# lautnerv.net
KiCad netlist of a schematic drawn in EAGLE
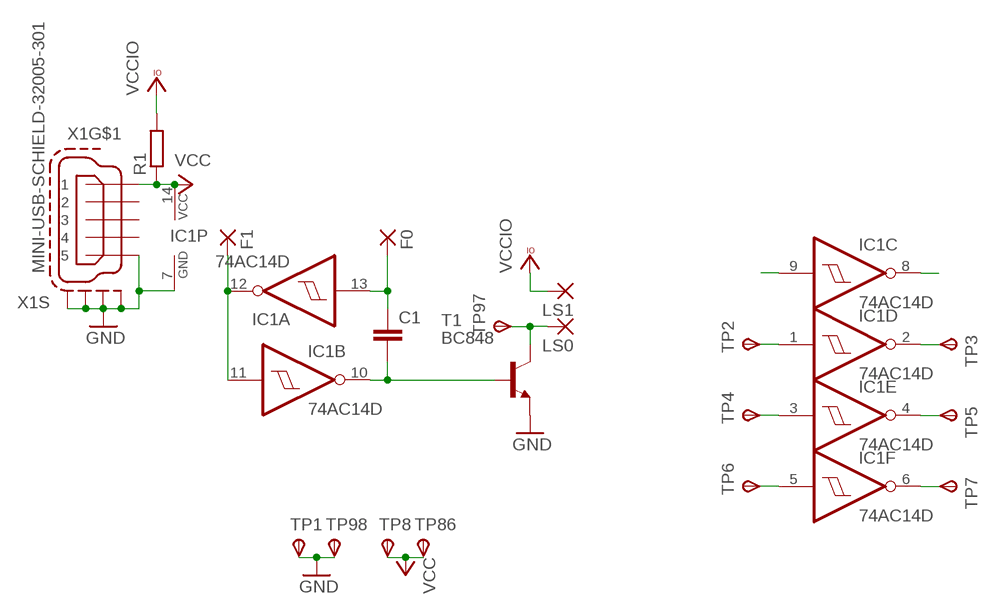
[diagram p0: schematic, sheet 1]
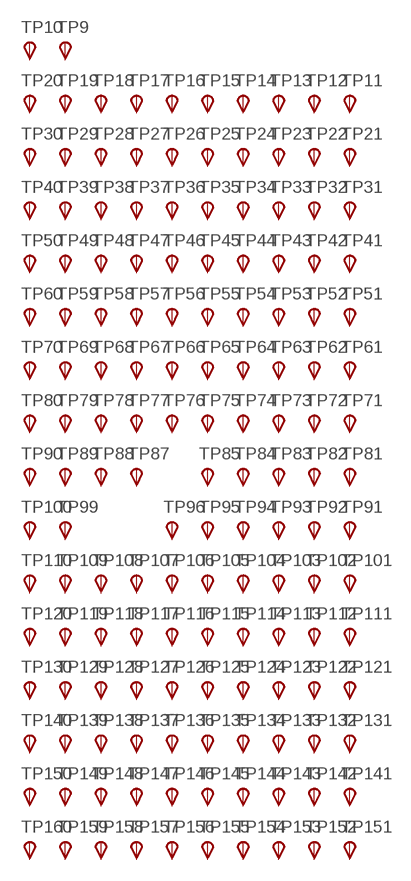
[diagram p1: schematic, sheet 2]

(export (version "E")
  (design (tool "Eeschema 10.0.6"))
  (components
    (comp (ref "TP9")
      (value "TPSTP12SQ")
      (footprint "eagle-import:TP12SQ")
      (libsource (lib "eagle-import") (part "TPSTP12SQ"))
    )
    (comp (ref "TP10")
      (value "TPSTP12SQ")
      (footprint "eagle-import:TP12SQ")
      (libsource (lib "eagle-import") (part "TPSTP12SQ"))
    )
    (comp (ref "TP11")
      (value "TPSTP12SQ")
      (footprint "eagle-import:TP12SQ")
      (libsource (lib "eagle-import") (part "TPSTP12SQ"))
    )
    (comp (ref "TP12")
      (value "TPSTP12SQ")
      (footprint "eagle-import:TP12SQ")
      (libsource (lib "eagle-import") (part "TPSTP12SQ"))
    )
    (comp (ref "TP13")
      (value "TPSTP12SQ")
      (footprint "eagle-import:TP12SQ")
      (libsource (lib "eagle-import") (part "TPSTP12SQ"))
    )
    (comp (ref "TP14")
      (value "TPSTP12SQ")
      (footprint "eagle-import:TP12SQ")
      (libsource (lib "eagle-import") (part "TPSTP12SQ"))
    )
    (comp (ref "TP15")
      (value "TPSTP12SQ")
      (footprint "eagle-import:TP12SQ")
      (libsource (lib "eagle-import") (part "TPSTP12SQ"))
    )
    (comp (ref "TP16")
      (value "TPSTP12SQ")
      (footprint "eagle-import:TP12SQ")
      (libsource (lib "eagle-import") (part "TPSTP12SQ"))
    )
    (comp (ref "TP17")
      (value "TPSTP12SQ")
      (footprint "eagle-import:TP12SQ")
      (libsource (lib "eagle-import") (part "TPSTP12SQ"))
    )
    (comp (ref "TP18")
      (value "TPSTP12SQ")
      (footprint "eagle-import:TP12SQ")
      (libsource (lib "eagle-import") (part "TPSTP12SQ"))
    )
    (comp (ref "TP19")
      (value "TPSTP12SQ")
      (footprint "eagle-import:TP12SQ")
      (libsource (lib "eagle-import") (part "TPSTP12SQ"))
    )
    (comp (ref "TP20")
      (value "TPSTP12SQ")
      (footprint "eagle-import:TP12SQ")
      (libsource (lib "eagle-import") (part "TPSTP12SQ"))
    )
    (comp (ref "TP21")
      (value "TPSTP12SQ")
      (footprint "eagle-import:TP12SQ")
      (libsource (lib "eagle-import") (part "TPSTP12SQ"))
    )
    (comp (ref "TP22")
      (value "TPSTP12SQ")
      (footprint "eagle-import:TP12SQ")
      (libsource (lib "eagle-import") (part "TPSTP12SQ"))
    )
    (comp (ref "TP23")
      (value "TPSTP12SQ")
      (footprint "eagle-import:TP12SQ")
      (libsource (lib "eagle-import") (part "TPSTP12SQ"))
    )
    (comp (ref "TP24")
      (value "TPSTP12SQ")
      (footprint "eagle-import:TP12SQ")
      (libsource (lib "eagle-import") (part "TPSTP12SQ"))
    )
    (comp (ref "TP25")
      (value "TPSTP12SQ")
      (footprint "eagle-import:TP12SQ")
      (libsource (lib "eagle-import") (part "TPSTP12SQ"))
    )
    (comp (ref "TP26")
      (value "TPSTP12SQ")
      (footprint "eagle-import:TP12SQ")
      (libsource (lib "eagle-import") (part "TPSTP12SQ"))
    )
    (comp (ref "TP27")
      (value "TPSTP12SQ")
      (footprint "eagle-import:TP12SQ")
      (libsource (lib "eagle-import") (part "TPSTP12SQ"))
    )
    (comp (ref "TP28")
      (value "TPSTP12SQ")
      (footprint "eagle-import:TP12SQ")
      (libsource (lib "eagle-import") (part "TPSTP12SQ"))
    )
    (comp (ref "TP29")
      (value "TPSTP12SQ")
      (footprint "eagle-import:TP12SQ")
      (libsource (lib "eagle-import") (part "TPSTP12SQ"))
    )
    (comp (ref "TP30")
      (value "TPSTP12SQ")
      (footprint "eagle-import:TP12SQ")
      (libsource (lib "eagle-import") (part "TPSTP12SQ"))
    )
    (comp (ref "TP31")
      (value "TPSTP12SQ")
      (footprint "eagle-import:TP12SQ")
      (libsource (lib "eagle-import") (part "TPSTP12SQ"))
    )
    (comp (ref "TP32")
      (value "TPSTP12SQ")
      (footprint "eagle-import:TP12SQ")
      (libsource (lib "eagle-import") (part "TPSTP12SQ"))
    )
    (comp (ref "TP33")
      (value "TPSTP12SQ")
      (footprint "eagle-import:TP12SQ")
      (libsource (lib "eagle-import") (part "TPSTP12SQ"))
    )
    (comp (ref "TP34")
      (value "TPSTP12SQ")
      (footprint "eagle-import:TP12SQ")
      (libsource (lib "eagle-import") (part "TPSTP12SQ"))
    )
    (comp (ref "TP35")
      (value "TPSTP12SQ")
      (footprint "eagle-import:TP12SQ")
      (libsource (lib "eagle-import") (part "TPSTP12SQ"))
    )
    (comp (ref "TP36")
      (value "TPSTP12SQ")
      (footprint "eagle-import:TP12SQ")
      (libsource (lib "eagle-import") (part "TPSTP12SQ"))
    )
    (comp (ref "TP37")
      (value "TPSTP12SQ")
      (footprint "eagle-import:TP12SQ")
      (libsource (lib "eagle-import") (part "TPSTP12SQ"))
    )
    (comp (ref "TP38")
      (value "TPSTP12SQ")
      (footprint "eagle-import:TP12SQ")
      (libsource (lib "eagle-import") (part "TPSTP12SQ"))
    )
    (comp (ref "TP39")
      (value "TPSTP12SQ")
      (footprint "eagle-import:TP12SQ")
      (libsource (lib "eagle-import") (part "TPSTP12SQ"))
    )
    (comp (ref "TP40")
      (value "TPSTP12SQ")
      (footprint "eagle-import:TP12SQ")
      (libsource (lib "eagle-import") (part "TPSTP12SQ"))
    )
    (comp (ref "TP41")
      (value "TPSTP12SQ")
      (footprint "eagle-import:TP12SQ")
      (libsource (lib "eagle-import") (part "TPSTP12SQ"))
    )
    (comp (ref "TP42")
      (value "TPSTP12SQ")
      (footprint "eagle-import:TP12SQ")
      (libsource (lib "eagle-import") (part "TPSTP12SQ"))
    )
    (comp (ref "TP43")
      (value "TPSTP12SQ")
      (footprint "eagle-import:TP12SQ")
      (libsource (lib "eagle-import") (part "TPSTP12SQ"))
    )
    (comp (ref "TP44")
      (value "TPSTP12SQ")
      (footprint "eagle-import:TP12SQ")
      (libsource (lib "eagle-import") (part "TPSTP12SQ"))
    )
    (comp (ref "TP45")
      (value "TPSTP12SQ")
      (footprint "eagle-import:TP12SQ")
      (libsource (lib "eagle-import") (part "TPSTP12SQ"))
    )
    (comp (ref "TP46")
      (value "TPSTP12SQ")
      (footprint "eagle-import:TP12SQ")
      (libsource (lib "eagle-import") (part "TPSTP12SQ"))
    )
    (comp (ref "TP47")
      (value "TPSTP12SQ")
      (footprint "eagle-import:TP12SQ")
      (libsource (lib "eagle-import") (part "TPSTP12SQ"))
    )
    (comp (ref "TP48")
      (value "TPSTP12SQ")
      (footprint "eagle-import:TP12SQ")
      (libsource (lib "eagle-import") (part "TPSTP12SQ"))
    )
    (comp (ref "TP49")
      (value "TPSTP12SQ")
      (footprint "eagle-import:TP12SQ")
      (libsource (lib "eagle-import") (part "TPSTP12SQ"))
    )
    (comp (ref "TP50")
      (value "TPSTP12SQ")
      (footprint "eagle-import:TP12SQ")
      (libsource (lib "eagle-import") (part "TPSTP12SQ"))
    )
    (comp (ref "TP51")
      (value "TPSTP12SQ")
      (footprint "eagle-import:TP12SQ")
      (libsource (lib "eagle-import") (part "TPSTP12SQ"))
    )
    (comp (ref "TP52")
      (value "TPSTP12SQ")
      (footprint "eagle-import:TP12SQ")
      (libsource (lib "eagle-import") (part "TPSTP12SQ"))
    )
    (comp (ref "TP53")
      (value "TPSTP12SQ")
      (footprint "eagle-import:TP12SQ")
      (libsource (lib "eagle-import") (part "TPSTP12SQ"))
    )
    (comp (ref "TP54")
      (value "TPSTP12SQ")
      (footprint "eagle-import:TP12SQ")
      (libsource (lib "eagle-import") (part "TPSTP12SQ"))
    )
    (comp (ref "TP55")
      (value "TPSTP12SQ")
      (footprint "eagle-import:TP12SQ")
      (libsource (lib "eagle-import") (part "TPSTP12SQ"))
    )
    (comp (ref "TP56")
      (value "TPSTP12SQ")
      (footprint "eagle-import:TP12SQ")
      (libsource (lib "eagle-import") (part "TPSTP12SQ"))
    )
    (comp (ref "TP57")
      (value "TPSTP12SQ")
      (footprint "eagle-import:TP12SQ")
      (libsource (lib "eagle-import") (part "TPSTP12SQ"))
    )
    (comp (ref "TP58")
      (value "TPSTP12SQ")
      (footprint "eagle-import:TP12SQ")
      (libsource (lib "eagle-import") (part "TPSTP12SQ"))
    )
    (comp (ref "TP59")
      (value "TPSTP12SQ")
      (footprint "eagle-import:TP12SQ")
      (libsource (lib "eagle-import") (part "TPSTP12SQ"))
    )
    (comp (ref "TP60")
      (value "TPSTP12SQ")
      (footprint "eagle-import:TP12SQ")
      (libsource (lib "eagle-import") (part "TPSTP12SQ"))
    )
    (comp (ref "TP61")
      (value "TPSTP12SQ")
      (footprint "eagle-import:TP12SQ")
      (libsource (lib "eagle-import") (part "TPSTP12SQ"))
    )
    (comp (ref "TP62")
      (value "TPSTP12SQ")
      (footprint "eagle-import:TP12SQ")
      (libsource (lib "eagle-import") (part "TPSTP12SQ"))
    )
    (comp (ref "TP63")
      (value "TPSTP12SQ")
      (footprint "eagle-import:TP12SQ")
      (libsource (lib "eagle-import") (part "TPSTP12SQ"))
    )
    (comp (ref "TP64")
      (value "TPSTP12SQ")
      (footprint "eagle-import:TP12SQ")
      (libsource (lib "eagle-import") (part "TPSTP12SQ"))
    )
    (comp (ref "TP65")
      (value "TPSTP12SQ")
      (footprint "eagle-import:TP12SQ")
      (libsource (lib "eagle-import") (part "TPSTP12SQ"))
    )
    (comp (ref "TP66")
      (value "TPSTP12SQ")
      (footprint "eagle-import:TP12SQ")
      (libsource (lib "eagle-import") (part "TPSTP12SQ"))
    )
    (comp (ref "TP67")
      (value "TPSTP12SQ")
      (footprint "eagle-import:TP12SQ")
      (libsource (lib "eagle-import") (part "TPSTP12SQ"))
    )
    (comp (ref "TP68")
      (value "TPSTP12SQ")
      (footprint "eagle-import:TP12SQ")
      (libsource (lib "eagle-import") (part "TPSTP12SQ"))
    )
    (comp (ref "TP69")
      (value "TPSTP12SQ")
      (footprint "eagle-import:TP12SQ")
      (libsource (lib "eagle-import") (part "TPSTP12SQ"))
    )
    (comp (ref "TP70")
      (value "TPSTP12SQ")
      (footprint "eagle-import:TP12SQ")
      (libsource (lib "eagle-import") (part "TPSTP12SQ"))
    )
    (comp (ref "TP71")
      (value "TPSTP12SQ")
      (footprint "eagle-import:TP12SQ")
      (libsource (lib "eagle-import") (part "TPSTP12SQ"))
    )
    (comp (ref "TP72")
      (value "TPSTP12SQ")
      (footprint "eagle-import:TP12SQ")
      (libsource (lib "eagle-import") (part "TPSTP12SQ"))
    )
    (comp (ref "TP73")
      (value "TPSTP12SQ")
      (footprint "eagle-import:TP12SQ")
      (libsource (lib "eagle-import") (part "TPSTP12SQ"))
    )
    (comp (ref "TP74")
      (value "TPSTP12SQ")
      (footprint "eagle-import:TP12SQ")
      (libsource (lib "eagle-import") (part "TPSTP12SQ"))
    )
    (comp (ref "TP75")
      (value "TPSTP12SQ")
      (footprint "eagle-import:TP12SQ")
      (libsource (lib "eagle-import") (part "TPSTP12SQ"))
    )
    (comp (ref "TP76")
      (value "TPSTP12SQ")
      (footprint "eagle-import:TP12SQ")
      (libsource (lib "eagle-import") (part "TPSTP12SQ"))
    )
    (comp (ref "TP77")
      (value "TPSTP12SQ")
      (footprint "eagle-import:TP12SQ")
      (libsource (lib "eagle-import") (part "TPSTP12SQ"))
    )
    (comp (ref "TP78")
      (value "TPSTP12SQ")
      (footprint "eagle-import:TP12SQ")
      (libsource (lib "eagle-import") (part "TPSTP12SQ"))
    )
    (comp (ref "TP79")
      (value "TPSTP12SQ")
      (footprint "eagle-import:TP12SQ")
      (libsource (lib "eagle-import") (part "TPSTP12SQ"))
    )
    (comp (ref "TP80")
      (value "TPSTP12SQ")
      (footprint "eagle-import:TP12SQ")
      (libsource (lib "eagle-import") (part "TPSTP12SQ"))
    )
    (comp (ref "TP81")
      (value "TPSTP12SQ")
      (footprint "eagle-import:TP12SQ")
      (libsource (lib "eagle-import") (part "TPSTP12SQ"))
    )
    (comp (ref "TP82")
      (value "TPSTP12SQ")
      (footprint "eagle-import:TP12SQ")
      (libsource (lib "eagle-import") (part "TPSTP12SQ"))
    )
    (comp (ref "TP83")
      (value "TPSTP12SQ")
      (footprint "eagle-import:TP12SQ")
      (libsource (lib "eagle-import") (part "TPSTP12SQ"))
    )
    (comp (ref "TP84")
      (value "TPSTP12SQ")
      (footprint "eagle-import:TP12SQ")
      (libsource (lib "eagle-import") (part "TPSTP12SQ"))
    )
    (comp (ref "TP85")
      (value "TPSTP12SQ")
      (footprint "eagle-import:TP12SQ")
      (libsource (lib "eagle-import") (part "TPSTP12SQ"))
    )
    (comp (ref "TP87")
      (value "TPSTP12SQ")
      (footprint "eagle-import:TP12SQ")
      (libsource (lib "eagle-import") (part "TPSTP12SQ"))
    )
    (comp (ref "TP88")
      (value "TPSTP12SQ")
      (footprint "eagle-import:TP12SQ")
      (libsource (lib "eagle-import") (part "TPSTP12SQ"))
    )
    (comp (ref "TP89")
      (value "TPSTP12SQ")
      (footprint "eagle-import:TP12SQ")
      (libsource (lib "eagle-import") (part "TPSTP12SQ"))
    )
    (comp (ref "TP90")
      (value "TPSTP12SQ")
      (footprint "eagle-import:TP12SQ")
      (libsource (lib "eagle-import") (part "TPSTP12SQ"))
    )
    (comp (ref "TP91")
      (value "TPSTP12SQ")
      (footprint "eagle-import:TP12SQ")
      (libsource (lib "eagle-import") (part "TPSTP12SQ"))
    )
    (comp (ref "TP92")
      (value "TPSTP12SQ")
      (footprint "eagle-import:TP12SQ")
      (libsource (lib "eagle-import") (part "TPSTP12SQ"))
    )
    (comp (ref "TP93")
      (value "TPSTP12SQ")
      (footprint "eagle-import:TP12SQ")
      (libsource (lib "eagle-import") (part "TPSTP12SQ"))
    )
    (comp (ref "TP94")
      (value "TPSTP12SQ")
      (footprint "eagle-import:TP12SQ")
      (libsource (lib "eagle-import") (part "TPSTP12SQ"))
    )
    (comp (ref "TP95")
      (value "TPSTP12SQ")
      (footprint "eagle-import:TP12SQ")
      (libsource (lib "eagle-import") (part "TPSTP12SQ"))
    )
    (comp (ref "TP96")
      (value "TPSTP12SQ")
      (footprint "eagle-import:TP12SQ")
      (libsource (lib "eagle-import") (part "TPSTP12SQ"))
    )
    (comp (ref "TP99")
      (value "TPSTP12SQ")
      (footprint "eagle-import:TP12SQ")
      (libsource (lib "eagle-import") (part "TPSTP12SQ"))
    )
    (comp (ref "TP100")
      (value "TPSTP12SQ")
      (footprint "eagle-import:TP12SQ")
      (libsource (lib "eagle-import") (part "TPSTP12SQ"))
    )
    (comp (ref "TP101")
      (value "TPSTP12SQ")
      (footprint "eagle-import:TP12SQ")
      (libsource (lib "eagle-import") (part "TPSTP12SQ"))
    )
    (comp (ref "TP102")
      (value "TPSTP12SQ")
      (footprint "eagle-import:TP12SQ")
      (libsource (lib "eagle-import") (part "TPSTP12SQ"))
    )
    (comp (ref "TP103")
      (value "TPSTP12SQ")
      (footprint "eagle-import:TP12SQ")
      (libsource (lib "eagle-import") (part "TPSTP12SQ"))
    )
    (comp (ref "TP104")
      (value "TPSTP12SQ")
      (footprint "eagle-import:TP12SQ")
      (libsource (lib "eagle-import") (part "TPSTP12SQ"))
    )
    (comp (ref "TP105")
      (value "TPSTP12SQ")
      (footprint "eagle-import:TP12SQ")
      (libsource (lib "eagle-import") (part "TPSTP12SQ"))
    )
    (comp (ref "TP106")
      (value "TPSTP12SQ")
      (footprint "eagle-import:TP12SQ")
      (libsource (lib "eagle-import") (part "TPSTP12SQ"))
    )
    (comp (ref "TP107")
      (value "TPSTP12SQ")
      (footprint "eagle-import:TP12SQ")
      (libsource (lib "eagle-import") (part "TPSTP12SQ"))
    )
    (comp (ref "TP108")
      (value "TPSTP12SQ")
      (footprint "eagle-import:TP12SQ")
      (libsource (lib "eagle-import") (part "TPSTP12SQ"))
    )
    (comp (ref "TP109")
      (value "TPSTP12SQ")
      (footprint "eagle-import:TP12SQ")
      (libsource (lib "eagle-import") (part "TPSTP12SQ"))
    )
    (comp (ref "TP110")
      (value "TPSTP12SQ")
      (footprint "eagle-import:TP12SQ")
      (libsource (lib "eagle-import") (part "TPSTP12SQ"))
    )
    (comp (ref "TP111")
      (value "TPSTP12SQ")
      (footprint "eagle-import:TP12SQ")
      (libsource (lib "eagle-import") (part "TPSTP12SQ"))
    )
    (comp (ref "TP112")
      (value "TPSTP12SQ")
      (footprint "eagle-import:TP12SQ")
      (libsource (lib "eagle-import") (part "TPSTP12SQ"))
    )
    (comp (ref "TP113")
      (value "TPSTP12SQ")
      (footprint "eagle-import:TP12SQ")
      (libsource (lib "eagle-import") (part "TPSTP12SQ"))
    )
    (comp (ref "TP114")
      (value "TPSTP12SQ")
      (footprint "eagle-import:TP12SQ")
      (libsource (lib "eagle-import") (part "TPSTP12SQ"))
    )
    (comp (ref "TP115")
      (value "TPSTP12SQ")
      (footprint "eagle-import:TP12SQ")
      (libsource (lib "eagle-import") (part "TPSTP12SQ"))
    )
    (comp (ref "TP116")
      (value "TPSTP12SQ")
      (footprint "eagle-import:TP12SQ")
      (libsource (lib "eagle-import") (part "TPSTP12SQ"))
    )
    (comp (ref "TP117")
      (value "TPSTP12SQ")
      (footprint "eagle-import:TP12SQ")
      (libsource (lib "eagle-import") (part "TPSTP12SQ"))
    )
    (comp (ref "TP118")
      (value "TPSTP12SQ")
      (footprint "eagle-import:TP12SQ")
      (libsource (lib "eagle-import") (part "TPSTP12SQ"))
    )
    (comp (ref "TP119")
      (value "TPSTP12SQ")
      (footprint "eagle-import:TP12SQ")
      (libsource (lib "eagle-import") (part "TPSTP12SQ"))
    )
    (comp (ref "TP120")
      (value "TPSTP12SQ")
      (footprint "eagle-import:TP12SQ")
      (libsource (lib "eagle-import") (part "TPSTP12SQ"))
    )
    (comp (ref "TP121")
      (value "TPSTP12SQ")
      (footprint "eagle-import:TP12SQ")
      (libsource (lib "eagle-import") (part "TPSTP12SQ"))
    )
    (comp (ref "TP122")
      (value "TPSTP12SQ")
      (footprint "eagle-import:TP12SQ")
      (libsource (lib "eagle-import") (part "TPSTP12SQ"))
    )
    (comp (ref "TP123")
      (value "TPSTP12SQ")
      (footprint "eagle-import:TP12SQ")
      (libsource (lib "eagle-import") (part "TPSTP12SQ"))
    )
    (comp (ref "TP124")
      (value "TPSTP12SQ")
      (footprint "eagle-import:TP12SQ")
      (libsource (lib "eagle-import") (part "TPSTP12SQ"))
    )
    (comp (ref "TP125")
      (value "TPSTP12SQ")
      (footprint "eagle-import:TP12SQ")
      (libsource (lib "eagle-import") (part "TPSTP12SQ"))
    )
    (comp (ref "TP126")
      (value "TPSTP12SQ")
      (footprint "eagle-import:TP12SQ")
      (libsource (lib "eagle-import") (part "TPSTP12SQ"))
    )
    (comp (ref "TP127")
      (value "TPSTP12SQ")
      (footprint "eagle-import:TP12SQ")
      (libsource (lib "eagle-import") (part "TPSTP12SQ"))
    )
    (comp (ref "TP128")
      (value "TPSTP12SQ")
      (footprint "eagle-import:TP12SQ")
      (libsource (lib "eagle-import") (part "TPSTP12SQ"))
    )
    (comp (ref "TP129")
      (value "TPSTP12SQ")
      (footprint "eagle-import:TP12SQ")
      (libsource (lib "eagle-import") (part "TPSTP12SQ"))
    )
    (comp (ref "TP130")
      (value "TPSTP12SQ")
      (footprint "eagle-import:TP12SQ")
      (libsource (lib "eagle-import") (part "TPSTP12SQ"))
    )
    (comp (ref "TP131")
      (value "TPSTP12SQ")
      (footprint "eagle-import:TP12SQ")
      (libsource (lib "eagle-import") (part "TPSTP12SQ"))
    )
    (comp (ref "TP132")
      (value "TPSTP12SQ")
      (footprint "eagle-import:TP12SQ")
      (libsource (lib "eagle-import") (part "TPSTP12SQ"))
    )
    (comp (ref "TP133")
      (value "TPSTP12SQ")
      (footprint "eagle-import:TP12SQ")
      (libsource (lib "eagle-import") (part "TPSTP12SQ"))
    )
    (comp (ref "TP134")
      (value "TPSTP12SQ")
      (footprint "eagle-import:TP12SQ")
      (libsource (lib "eagle-import") (part "TPSTP12SQ"))
    )
    (comp (ref "TP135")
      (value "TPSTP12SQ")
      (footprint "eagle-import:TP12SQ")
      (libsource (lib "eagle-import") (part "TPSTP12SQ"))
    )
    (comp (ref "TP136")
      (value "TPSTP12SQ")
      (footprint "eagle-import:TP12SQ")
      (libsource (lib "eagle-import") (part "TPSTP12SQ"))
    )
    (comp (ref "TP137")
      (value "TPSTP12SQ")
      (footprint "eagle-import:TP12SQ")
      (libsource (lib "eagle-import") (part "TPSTP12SQ"))
    )
    (comp (ref "TP138")
      (value "TPSTP12SQ")
      (footprint "eagle-import:TP12SQ")
      (libsource (lib "eagle-import") (part "TPSTP12SQ"))
    )
    (comp (ref "TP139")
      (value "TPSTP12SQ")
      (footprint "eagle-import:TP12SQ")
      (libsource (lib "eagle-import") (part "TPSTP12SQ"))
    )
    (comp (ref "TP140")
      (value "TPSTP12SQ")
      (footprint "eagle-import:TP12SQ")
      (libsource (lib "eagle-import") (part "TPSTP12SQ"))
    )
    (comp (ref "TP141")
      (value "TPSTP12SQ")
      (footprint "eagle-import:TP12SQ")
      (libsource (lib "eagle-import") (part "TPSTP12SQ"))
    )
    (comp (ref "TP142")
      (value "TPSTP12SQ")
      (footprint "eagle-import:TP12SQ")
      (libsource (lib "eagle-import") (part "TPSTP12SQ"))
    )
    (comp (ref "TP143")
      (value "TPSTP12SQ")
      (footprint "eagle-import:TP12SQ")
      (libsource (lib "eagle-import") (part "TPSTP12SQ"))
    )
    (comp (ref "TP144")
      (value "TPSTP12SQ")
      (footprint "eagle-import:TP12SQ")
      (libsource (lib "eagle-import") (part "TPSTP12SQ"))
    )
    (comp (ref "TP145")
      (value "TPSTP12SQ")
      (footprint "eagle-import:TP12SQ")
      (libsource (lib "eagle-import") (part "TPSTP12SQ"))
    )
    (comp (ref "TP146")
      (value "TPSTP12SQ")
      (footprint "eagle-import:TP12SQ")
      (libsource (lib "eagle-import") (part "TPSTP12SQ"))
    )
    (comp (ref "TP147")
      (value "TPSTP12SQ")
      (footprint "eagle-import:TP12SQ")
      (libsource (lib "eagle-import") (part "TPSTP12SQ"))
    )
    (comp (ref "TP148")
      (value "TPSTP12SQ")
      (footprint "eagle-import:TP12SQ")
      (libsource (lib "eagle-import") (part "TPSTP12SQ"))
    )
    (comp (ref "TP149")
      (value "TPSTP12SQ")
      (footprint "eagle-import:TP12SQ")
      (libsource (lib "eagle-import") (part "TPSTP12SQ"))
    )
    (comp (ref "TP150")
      (value "TPSTP12SQ")
      (footprint "eagle-import:TP12SQ")
      (libsource (lib "eagle-import") (part "TPSTP12SQ"))
    )
    (comp (ref "TP151")
      (value "TPSTP12SQ")
      (footprint "eagle-import:TP12SQ")
      (libsource (lib "eagle-import") (part "TPSTP12SQ"))
    )
    (comp (ref "TP152")
      (value "TPSTP12SQ")
      (footprint "eagle-import:TP12SQ")
      (libsource (lib "eagle-import") (part "TPSTP12SQ"))
    )
    (comp (ref "TP153")
      (value "TPSTP12SQ")
      (footprint "eagle-import:TP12SQ")
      (libsource (lib "eagle-import") (part "TPSTP12SQ"))
    )
    (comp (ref "TP154")
      (value "TPSTP12SQ")
      (footprint "eagle-import:TP12SQ")
      (libsource (lib "eagle-import") (part "TPSTP12SQ"))
    )
    (comp (ref "TP155")
      (value "TPSTP12SQ")
      (footprint "eagle-import:TP12SQ")
      (libsource (lib "eagle-import") (part "TPSTP12SQ"))
    )
    (comp (ref "TP156")
      (value "TPSTP12SQ")
      (footprint "eagle-import:TP12SQ")
      (libsource (lib "eagle-import") (part "TPSTP12SQ"))
    )
    (comp (ref "TP157")
      (value "TPSTP12SQ")
      (footprint "eagle-import:TP12SQ")
      (libsource (lib "eagle-import") (part "TPSTP12SQ"))
    )
    (comp (ref "TP158")
      (value "TPSTP12SQ")
      (footprint "eagle-import:TP12SQ")
      (libsource (lib "eagle-import") (part "TPSTP12SQ"))
    )
    (comp (ref "TP159")
      (value "TPSTP12SQ")
      (footprint "eagle-import:TP12SQ")
      (libsource (lib "eagle-import") (part "TPSTP12SQ"))
    )
    (comp (ref "TP160")
      (value "TPSTP12SQ")
      (footprint "eagle-import:TP12SQ")
      (libsource (lib "eagle-import") (part "TPSTP12SQ"))
    )
    (comp (ref "C1")
      (value "C-EUC1206K")
      (footprint "eagle-import:C1206K")
      (libsource (lib "eagle-import") (part "C-EUC1206K"))
    )
    (comp (ref "F0")
      (value "SMD5")
      (footprint "eagle-import:SMD2,54-5,08")
      (libsource (lib "eagle-import") (part "SMD5"))
    )
    (comp (ref "F1")
      (value "SMD5")
      (footprint "eagle-import:SMD2,54-5,08")
      (libsource (lib "eagle-import") (part "SMD5"))
    )
    (comp (ref "IC1")
      (value "74AC14D")
      (footprint "eagle-import:SO14")
      (libsource (lib "eagle-import") (part "7414DAC"))
    )
    (comp (ref "LS0")
      (value "SMD5")
      (footprint "eagle-import:SMD2,54-5,08")
      (libsource (lib "eagle-import") (part "SMD5"))
    )
    (comp (ref "LS1")
      (value "SMD5")
      (footprint "eagle-import:SMD2,54-5,08")
      (libsource (lib "eagle-import") (part "SMD5"))
    )
    (comp (ref "R1")
      (value "R-EU_M1206")
      (footprint "eagle-import:M1206")
      (libsource (lib "eagle-import") (part "R-EU_M1206"))
    )
    (comp (ref "T1")
      (value "BC848")
      (footprint "eagle-import:SOT23")
      (libsource (lib "eagle-import") (part "BC848SMDA"))
    )
    (comp (ref "TP1")
      (value "TPSTP12SQ")
      (footprint "eagle-import:TP12SQ")
      (libsource (lib "eagle-import") (part "TPSTP12SQ"))
    )
    (comp (ref "TP2")
      (value "TPSTP12SQ")
      (footprint "eagle-import:TP12SQ")
      (libsource (lib "eagle-import") (part "TPSTP12SQ"))
    )
    (comp (ref "TP3")
      (value "TPSTP12SQ")
      (footprint "eagle-import:TP12SQ")
      (libsource (lib "eagle-import") (part "TPSTP12SQ"))
    )
    (comp (ref "TP4")
      (value "TPSTP12SQ")
      (footprint "eagle-import:TP12SQ")
      (libsource (lib "eagle-import") (part "TPSTP12SQ"))
    )
    (comp (ref "TP5")
      (value "TPSTP12SQ")
      (footprint "eagle-import:TP12SQ")
      (libsource (lib "eagle-import") (part "TPSTP12SQ"))
    )
    (comp (ref "TP6")
      (value "TPSTP12SQ")
      (footprint "eagle-import:TP12SQ")
      (libsource (lib "eagle-import") (part "TPSTP12SQ"))
    )
    (comp (ref "TP7")
      (value "TPSTP12SQ")
      (footprint "eagle-import:TP12SQ")
      (libsource (lib "eagle-import") (part "TPSTP12SQ"))
    )
    (comp (ref "TP8")
      (value "TPSTP12SQ")
      (footprint "eagle-import:TP12SQ")
      (libsource (lib "eagle-import") (part "TPSTP12SQ"))
    )
    (comp (ref "TP86")
      (value "TPSTP12SQ")
      (footprint "eagle-import:TP12SQ")
      (libsource (lib "eagle-import") (part "TPSTP12SQ"))
    )
    (comp (ref "TP97")
      (value "TPSTP12SQ")
      (footprint "eagle-import:TP12SQ")
      (libsource (lib "eagle-import") (part "TPSTP12SQ"))
    )
    (comp (ref "TP98")
      (value "TPSTP12SQ")
      (footprint "eagle-import:TP12SQ")
      (libsource (lib "eagle-import") (part "TPSTP12SQ"))
    )
    (comp (ref "X1")
      (value "MINI-USB-SCHIELD-32005-301")
      (footprint "eagle-import:32005-301")
      (libsource (lib "eagle-import") (part "MINI-USB-SCHIELD-32005-301"))
    )
  )
  (nets
    (net (code "1") (name "GND") (class "Default")
      (node (ref "IC1") (pin "7") (pinfunction "GND_7") (pintype "power_in"))
      (node (ref "T1") (pin "2") (pinfunction "E_2") (pintype "passive"))
      (node (ref "TP1") (pin "TP") (pinfunction "PP_TP") (pintype "input"))
      (node (ref "TP98") (pin "TP") (pinfunction "PP_TP") (pintype "input"))
      (node (ref "X1") (pin "5") (pinfunction "5_5") (pintype "passive"))
      (node (ref "X1") (pin "M1") (pinfunction "S1_M1") (pintype "passive"))
      (node (ref "X1") (pin "M2") (pinfunction "S2_M2") (pintype "passive"))
      (node (ref "X1") (pin "M3") (pinfunction "S3_M3") (pintype "passive"))
      (node (ref "X1") (pin "M4") (pinfunction "S4_M4") (pintype "passive"))
    )
    (net (code "2") (name "Net-(F0-P)") (class "Default")
      (node (ref "C1") (pin "1") (pinfunction "1_1") (pintype "passive"))
      (node (ref "F0") (pin "1") (pinfunction "P_1") (pintype "passive"))
      (node (ref "IC1") (pin "13") (pinfunction "I_13") (pintype "input"))
    )
    (net (code "3") (name "Net-(F1-P)") (class "Default")
      (node (ref "F1") (pin "1") (pinfunction "P_1") (pintype "passive"))
      (node (ref "IC1") (pin "11") (pinfunction "I_11") (pintype "input"))
      (node (ref "IC1") (pin "12") (pinfunction "O_12") (pintype "output"))
    )
    (net (code "4") (name "Net-(IC1B-O)") (class "Default")
      (node (ref "C1") (pin "2") (pinfunction "2_2") (pintype "passive"))
      (node (ref "IC1") (pin "10") (pinfunction "O_10") (pintype "output"))
      (node (ref "T1") (pin "1") (pinfunction "B_1") (pintype "passive"))
    )
    (net (code "5") (name "Net-(IC1D-I)") (class "Default")
      (node (ref "IC1") (pin "1") (pinfunction "I_1") (pintype "input"))
      (node (ref "TP2") (pin "TP") (pinfunction "PP_TP") (pintype "input"))
    )
    (net (code "6") (name "Net-(IC1D-O)") (class "Default")
      (node (ref "IC1") (pin "2") (pinfunction "O_2") (pintype "output"))
      (node (ref "TP3") (pin "TP") (pinfunction "PP_TP") (pintype "input"))
    )
    (net (code "7") (name "Net-(IC1E-I)") (class "Default")
      (node (ref "IC1") (pin "3") (pinfunction "I_3") (pintype "input"))
      (node (ref "TP4") (pin "TP") (pinfunction "PP_TP") (pintype "input"))
    )
    (net (code "8") (name "Net-(IC1E-O)") (class "Default")
      (node (ref "IC1") (pin "4") (pinfunction "O_4") (pintype "output"))
      (node (ref "TP5") (pin "TP") (pinfunction "PP_TP") (pintype "input"))
    )
    (net (code "9") (name "Net-(IC1F-I)") (class "Default")
      (node (ref "IC1") (pin "5") (pinfunction "I_5") (pintype "input"))
      (node (ref "TP6") (pin "TP") (pinfunction "PP_TP") (pintype "input"))
    )
    (net (code "10") (name "Net-(IC1F-O)") (class "Default")
      (node (ref "IC1") (pin "6") (pinfunction "O_6") (pintype "output"))
      (node (ref "TP7") (pin "TP") (pinfunction "PP_TP") (pintype "input"))
    )
    (net (code "11") (name "Net-(LS0-P)") (class "Default")
      (node (ref "LS0") (pin "1") (pinfunction "P_1") (pintype "passive"))
      (node (ref "T1") (pin "3") (pinfunction "C_3") (pintype "passive"))
      (node (ref "TP97") (pin "TP") (pinfunction "PP_TP") (pintype "input"))
    )
    (net (code "12") (name "VCC") (class "Default")
      (node (ref "IC1") (pin "14") (pinfunction "VCC_14") (pintype "power_in"))
      (node (ref "R1") (pin "1") (pinfunction "1_1") (pintype "passive"))
      (node (ref "TP8") (pin "TP") (pinfunction "PP_TP") (pintype "input"))
      (node (ref "TP86") (pin "TP") (pinfunction "PP_TP") (pintype "input"))
      (node (ref "X1") (pin "1") (pinfunction "1_1") (pintype "passive"))
    )
    (net (code "13") (name "VCCIO") (class "Default")
      (node (ref "LS1") (pin "1") (pinfunction "P_1") (pintype "passive"))
      (node (ref "R1") (pin "2") (pinfunction "2_2") (pintype "passive"))
    )
    (net (code "14") (name "unconnected-(IC1C-I-Pad9)") (class "Default")
      (node (ref "IC1") (pin "9") (pinfunction "I_9") (pintype "input"))
    )
    (net (code "15") (name "unconnected-(IC1C-O-Pad8)") (class "Default")
      (node (ref "IC1") (pin "8") (pinfunction "O_8") (pintype "output"))
    )
    (net (code "16") (name "unconnected-(TP9-PP-PadTP)") (class "Default")
      (node (ref "TP9") (pin "TP") (pinfunction "PP_TP") (pintype "input"))
    )
    (net (code "17") (name "unconnected-(TP10-PP-PadTP)") (class "Default")
      (node (ref "TP10") (pin "TP") (pinfunction "PP_TP") (pintype "input"))
    )
    (net (code "18") (name "unconnected-(TP11-PP-PadTP)") (class "Default")
      (node (ref "TP11") (pin "TP") (pinfunction "PP_TP") (pintype "input"))
    )
    (net (code "19") (name "unconnected-(TP12-PP-PadTP)") (class "Default")
      (node (ref "TP12") (pin "TP") (pinfunction "PP_TP") (pintype "input"))
    )
    (net (code "20") (name "unconnected-(TP13-PP-PadTP)") (class "Default")
      (node (ref "TP13") (pin "TP") (pinfunction "PP_TP") (pintype "input"))
    )
    (net (code "21") (name "unconnected-(TP14-PP-PadTP)") (class "Default")
      (node (ref "TP14") (pin "TP") (pinfunction "PP_TP") (pintype "input"))
    )
    (net (code "22") (name "unconnected-(TP15-PP-PadTP)") (class "Default")
      (node (ref "TP15") (pin "TP") (pinfunction "PP_TP") (pintype "input"))
    )
    (net (code "23") (name "unconnected-(TP16-PP-PadTP)") (class "Default")
      (node (ref "TP16") (pin "TP") (pinfunction "PP_TP") (pintype "input"))
    )
    (net (code "24") (name "unconnected-(TP17-PP-PadTP)") (class "Default")
      (node (ref "TP17") (pin "TP") (pinfunction "PP_TP") (pintype "input"))
    )
    (net (code "25") (name "unconnected-(TP18-PP-PadTP)") (class "Default")
      (node (ref "TP18") (pin "TP") (pinfunction "PP_TP") (pintype "input"))
    )
    (net (code "26") (name "unconnected-(TP19-PP-PadTP)") (class "Default")
      (node (ref "TP19") (pin "TP") (pinfunction "PP_TP") (pintype "input"))
    )
    (net (code "27") (name "unconnected-(TP20-PP-PadTP)") (class "Default")
      (node (ref "TP20") (pin "TP") (pinfunction "PP_TP") (pintype "input"))
    )
    (net (code "28") (name "unconnected-(TP21-PP-PadTP)") (class "Default")
      (node (ref "TP21") (pin "TP") (pinfunction "PP_TP") (pintype "input"))
    )
    (net (code "29") (name "unconnected-(TP22-PP-PadTP)") (class "Default")
      (node (ref "TP22") (pin "TP") (pinfunction "PP_TP") (pintype "input"))
    )
    (net (code "30") (name "unconnected-(TP23-PP-PadTP)") (class "Default")
      (node (ref "TP23") (pin "TP") (pinfunction "PP_TP") (pintype "input"))
    )
    (net (code "31") (name "unconnected-(TP24-PP-PadTP)") (class "Default")
      (node (ref "TP24") (pin "TP") (pinfunction "PP_TP") (pintype "input"))
    )
    (net (code "32") (name "unconnected-(TP25-PP-PadTP)") (class "Default")
      (node (ref "TP25") (pin "TP") (pinfunction "PP_TP") (pintype "input"))
    )
    (net (code "33") (name "unconnected-(TP26-PP-PadTP)") (class "Default")
      (node (ref "TP26") (pin "TP") (pinfunction "PP_TP") (pintype "input"))
    )
    (net (code "34") (name "unconnected-(TP27-PP-PadTP)") (class "Default")
      (node (ref "TP27") (pin "TP") (pinfunction "PP_TP") (pintype "input"))
    )
    (net (code "35") (name "unconnected-(TP28-PP-PadTP)") (class "Default")
      (node (ref "TP28") (pin "TP") (pinfunction "PP_TP") (pintype "input"))
    )
    (net (code "36") (name "unconnected-(TP29-PP-PadTP)") (class "Default")
      (node (ref "TP29") (pin "TP") (pinfunction "PP_TP") (pintype "input"))
    )
    (net (code "37") (name "unconnected-(TP30-PP-PadTP)") (class "Default")
      (node (ref "TP30") (pin "TP") (pinfunction "PP_TP") (pintype "input"))
    )
    (net (code "38") (name "unconnected-(TP31-PP-PadTP)") (class "Default")
      (node (ref "TP31") (pin "TP") (pinfunction "PP_TP") (pintype "input"))
    )
    (net (code "39") (name "unconnected-(TP32-PP-PadTP)") (class "Default")
      (node (ref "TP32") (pin "TP") (pinfunction "PP_TP") (pintype "input"))
    )
    (net (code "40") (name "unconnected-(TP33-PP-PadTP)") (class "Default")
      (node (ref "TP33") (pin "TP") (pinfunction "PP_TP") (pintype "input"))
    )
    (net (code "41") (name "unconnected-(TP34-PP-PadTP)") (class "Default")
      (node (ref "TP34") (pin "TP") (pinfunction "PP_TP") (pintype "input"))
    )
    (net (code "42") (name "unconnected-(TP35-PP-PadTP)") (class "Default")
      (node (ref "TP35") (pin "TP") (pinfunction "PP_TP") (pintype "input"))
    )
    (net (code "43") (name "unconnected-(TP36-PP-PadTP)") (class "Default")
      (node (ref "TP36") (pin "TP") (pinfunction "PP_TP") (pintype "input"))
    )
    (net (code "44") (name "unconnected-(TP37-PP-PadTP)") (class "Default")
      (node (ref "TP37") (pin "TP") (pinfunction "PP_TP") (pintype "input"))
    )
    (net (code "45") (name "unconnected-(TP38-PP-PadTP)") (class "Default")
      (node (ref "TP38") (pin "TP") (pinfunction "PP_TP") (pintype "input"))
    )
    (net (code "46") (name "unconnected-(TP39-PP-PadTP)") (class "Default")
      (node (ref "TP39") (pin "TP") (pinfunction "PP_TP") (pintype "input"))
    )
    (net (code "47") (name "unconnected-(TP40-PP-PadTP)") (class "Default")
      (node (ref "TP40") (pin "TP") (pinfunction "PP_TP") (pintype "input"))
    )
    (net (code "48") (name "unconnected-(TP41-PP-PadTP)") (class "Default")
      (node (ref "TP41") (pin "TP") (pinfunction "PP_TP") (pintype "input"))
    )
    (net (code "49") (name "unconnected-(TP42-PP-PadTP)") (class "Default")
      (node (ref "TP42") (pin "TP") (pinfunction "PP_TP") (pintype "input"))
    )
    (net (code "50") (name "unconnected-(TP43-PP-PadTP)") (class "Default")
      (node (ref "TP43") (pin "TP") (pinfunction "PP_TP") (pintype "input"))
    )
    (net (code "51") (name "unconnected-(TP44-PP-PadTP)") (class "Default")
      (node (ref "TP44") (pin "TP") (pinfunction "PP_TP") (pintype "input"))
    )
    (net (code "52") (name "unconnected-(TP45-PP-PadTP)") (class "Default")
      (node (ref "TP45") (pin "TP") (pinfunction "PP_TP") (pintype "input"))
    )
    (net (code "53") (name "unconnected-(TP46-PP-PadTP)") (class "Default")
      (node (ref "TP46") (pin "TP") (pinfunction "PP_TP") (pintype "input"))
    )
    (net (code "54") (name "unconnected-(TP47-PP-PadTP)") (class "Default")
      (node (ref "TP47") (pin "TP") (pinfunction "PP_TP") (pintype "input"))
    )
    (net (code "55") (name "unconnected-(TP48-PP-PadTP)") (class "Default")
      (node (ref "TP48") (pin "TP") (pinfunction "PP_TP") (pintype "input"))
    )
    (net (code "56") (name "unconnected-(TP49-PP-PadTP)") (class "Default")
      (node (ref "TP49") (pin "TP") (pinfunction "PP_TP") (pintype "input"))
    )
    (net (code "57") (name "unconnected-(TP50-PP-PadTP)") (class "Default")
      (node (ref "TP50") (pin "TP") (pinfunction "PP_TP") (pintype "input"))
    )
    (net (code "58") (name "unconnected-(TP51-PP-PadTP)") (class "Default")
      (node (ref "TP51") (pin "TP") (pinfunction "PP_TP") (pintype "input"))
    )
    (net (code "59") (name "unconnected-(TP52-PP-PadTP)") (class "Default")
      (node (ref "TP52") (pin "TP") (pinfunction "PP_TP") (pintype "input"))
    )
    (net (code "60") (name "unconnected-(TP53-PP-PadTP)") (class "Default")
      (node (ref "TP53") (pin "TP") (pinfunction "PP_TP") (pintype "input"))
    )
    (net (code "61") (name "unconnected-(TP54-PP-PadTP)") (class "Default")
      (node (ref "TP54") (pin "TP") (pinfunction "PP_TP") (pintype "input"))
    )
    (net (code "62") (name "unconnected-(TP55-PP-PadTP)") (class "Default")
      (node (ref "TP55") (pin "TP") (pinfunction "PP_TP") (pintype "input"))
    )
    (net (code "63") (name "unconnected-(TP56-PP-PadTP)") (class "Default")
      (node (ref "TP56") (pin "TP") (pinfunction "PP_TP") (pintype "input"))
    )
    (net (code "64") (name "unconnected-(TP57-PP-PadTP)") (class "Default")
      (node (ref "TP57") (pin "TP") (pinfunction "PP_TP") (pintype "input"))
    )
    (net (code "65") (name "unconnected-(TP58-PP-PadTP)") (class "Default")
      (node (ref "TP58") (pin "TP") (pinfunction "PP_TP") (pintype "input"))
    )
    (net (code "66") (name "unconnected-(TP59-PP-PadTP)") (class "Default")
      (node (ref "TP59") (pin "TP") (pinfunction "PP_TP") (pintype "input"))
    )
    (net (code "67") (name "unconnected-(TP60-PP-PadTP)") (class "Default")
      (node (ref "TP60") (pin "TP") (pinfunction "PP_TP") (pintype "input"))
    )
    (net (code "68") (name "unconnected-(TP61-PP-PadTP)") (class "Default")
      (node (ref "TP61") (pin "TP") (pinfunction "PP_TP") (pintype "input"))
    )
    (net (code "69") (name "unconnected-(TP62-PP-PadTP)") (class "Default")
      (node (ref "TP62") (pin "TP") (pinfunction "PP_TP") (pintype "input"))
    )
    (net (code "70") (name "unconnected-(TP63-PP-PadTP)") (class "Default")
      (node (ref "TP63") (pin "TP") (pinfunction "PP_TP") (pintype "input"))
    )
    (net (code "71") (name "unconnected-(TP64-PP-PadTP)") (class "Default")
      (node (ref "TP64") (pin "TP") (pinfunction "PP_TP") (pintype "input"))
    )
    (net (code "72") (name "unconnected-(TP65-PP-PadTP)") (class "Default")
      (node (ref "TP65") (pin "TP") (pinfunction "PP_TP") (pintype "input"))
    )
    (net (code "73") (name "unconnected-(TP66-PP-PadTP)") (class "Default")
      (node (ref "TP66") (pin "TP") (pinfunction "PP_TP") (pintype "input"))
    )
    (net (code "74") (name "unconnected-(TP67-PP-PadTP)") (class "Default")
      (node (ref "TP67") (pin "TP") (pinfunction "PP_TP") (pintype "input"))
    )
    (net (code "75") (name "unconnected-(TP68-PP-PadTP)") (class "Default")
      (node (ref "TP68") (pin "TP") (pinfunction "PP_TP") (pintype "input"))
    )
    (net (code "76") (name "unconnected-(TP69-PP-PadTP)") (class "Default")
      (node (ref "TP69") (pin "TP") (pinfunction "PP_TP") (pintype "input"))
    )
    (net (code "77") (name "unconnected-(TP70-PP-PadTP)") (class "Default")
      (node (ref "TP70") (pin "TP") (pinfunction "PP_TP") (pintype "input"))
    )
    (net (code "78") (name "unconnected-(TP71-PP-PadTP)") (class "Default")
      (node (ref "TP71") (pin "TP") (pinfunction "PP_TP") (pintype "input"))
    )
    (net (code "79") (name "unconnected-(TP72-PP-PadTP)") (class "Default")
      (node (ref "TP72") (pin "TP") (pinfunction "PP_TP") (pintype "input"))
    )
    (net (code "80") (name "unconnected-(TP73-PP-PadTP)") (class "Default")
      (node (ref "TP73") (pin "TP") (pinfunction "PP_TP") (pintype "input"))
    )
    (net (code "81") (name "unconnected-(TP74-PP-PadTP)") (class "Default")
      (node (ref "TP74") (pin "TP") (pinfunction "PP_TP") (pintype "input"))
    )
    (net (code "82") (name "unconnected-(TP75-PP-PadTP)") (class "Default")
      (node (ref "TP75") (pin "TP") (pinfunction "PP_TP") (pintype "input"))
    )
    (net (code "83") (name "unconnected-(TP76-PP-PadTP)") (class "Default")
      (node (ref "TP76") (pin "TP") (pinfunction "PP_TP") (pintype "input"))
    )
    (net (code "84") (name "unconnected-(TP77-PP-PadTP)") (class "Default")
      (node (ref "TP77") (pin "TP") (pinfunction "PP_TP") (pintype "input"))
    )
    (net (code "85") (name "unconnected-(TP78-PP-PadTP)") (class "Default")
      (node (ref "TP78") (pin "TP") (pinfunction "PP_TP") (pintype "input"))
    )
    (net (code "86") (name "unconnected-(TP79-PP-PadTP)") (class "Default")
      (node (ref "TP79") (pin "TP") (pinfunction "PP_TP") (pintype "input"))
    )
    (net (code "87") (name "unconnected-(TP80-PP-PadTP)") (class "Default")
      (node (ref "TP80") (pin "TP") (pinfunction "PP_TP") (pintype "input"))
    )
    (net (code "88") (name "unconnected-(TP81-PP-PadTP)") (class "Default")
      (node (ref "TP81") (pin "TP") (pinfunction "PP_TP") (pintype "input"))
    )
    (net (code "89") (name "unconnected-(TP82-PP-PadTP)") (class "Default")
      (node (ref "TP82") (pin "TP") (pinfunction "PP_TP") (pintype "input"))
    )
    (net (code "90") (name "unconnected-(TP83-PP-PadTP)") (class "Default")
      (node (ref "TP83") (pin "TP") (pinfunction "PP_TP") (pintype "input"))
    )
    (net (code "91") (name "unconnected-(TP84-PP-PadTP)") (class "Default")
      (node (ref "TP84") (pin "TP") (pinfunction "PP_TP") (pintype "input"))
    )
    (net (code "92") (name "unconnected-(TP85-PP-PadTP)") (class "Default")
      (node (ref "TP85") (pin "TP") (pinfunction "PP_TP") (pintype "input"))
    )
    (net (code "93") (name "unconnected-(TP87-PP-PadTP)") (class "Default")
      (node (ref "TP87") (pin "TP") (pinfunction "PP_TP") (pintype "input"))
    )
    (net (code "94") (name "unconnected-(TP88-PP-PadTP)") (class "Default")
      (node (ref "TP88") (pin "TP") (pinfunction "PP_TP") (pintype "input"))
    )
    (net (code "95") (name "unconnected-(TP89-PP-PadTP)") (class "Default")
      (node (ref "TP89") (pin "TP") (pinfunction "PP_TP") (pintype "input"))
    )
    (net (code "96") (name "unconnected-(TP90-PP-PadTP)") (class "Default")
      (node (ref "TP90") (pin "TP") (pinfunction "PP_TP") (pintype "input"))
    )
    (net (code "97") (name "unconnected-(TP91-PP-PadTP)") (class "Default")
      (node (ref "TP91") (pin "TP") (pinfunction "PP_TP") (pintype "input"))
    )
    (net (code "98") (name "unconnected-(TP92-PP-PadTP)") (class "Default")
      (node (ref "TP92") (pin "TP") (pinfunction "PP_TP") (pintype "input"))
    )
    (net (code "99") (name "unconnected-(TP93-PP-PadTP)") (class "Default")
      (node (ref "TP93") (pin "TP") (pinfunction "PP_TP") (pintype "input"))
    )
    (net (code "100") (name "unconnected-(TP94-PP-PadTP)") (class "Default")
      (node (ref "TP94") (pin "TP") (pinfunction "PP_TP") (pintype "input"))
    )
    (net (code "101") (name "unconnected-(TP95-PP-PadTP)") (class "Default")
      (node (ref "TP95") (pin "TP") (pinfunction "PP_TP") (pintype "input"))
    )
    (net (code "102") (name "unconnected-(TP96-PP-PadTP)") (class "Default")
      (node (ref "TP96") (pin "TP") (pinfunction "PP_TP") (pintype "input"))
    )
    (net (code "103") (name "unconnected-(TP99-PP-PadTP)") (class "Default")
      (node (ref "TP99") (pin "TP") (pinfunction "PP_TP") (pintype "input"))
    )
    (net (code "104") (name "unconnected-(TP100-PP-PadTP)") (class "Default")
      (node (ref "TP100") (pin "TP") (pinfunction "PP_TP") (pintype "input"))
    )
    (net (code "105") (name "unconnected-(TP101-PP-PadTP)") (class "Default")
      (node (ref "TP101") (pin "TP") (pinfunction "PP_TP") (pintype "input"))
    )
    (net (code "106") (name "unconnected-(TP102-PP-PadTP)") (class "Default")
      (node (ref "TP102") (pin "TP") (pinfunction "PP_TP") (pintype "input"))
    )
    (net (code "107") (name "unconnected-(TP103-PP-PadTP)") (class "Default")
      (node (ref "TP103") (pin "TP") (pinfunction "PP_TP") (pintype "input"))
    )
    (net (code "108") (name "unconnected-(TP104-PP-PadTP)") (class "Default")
      (node (ref "TP104") (pin "TP") (pinfunction "PP_TP") (pintype "input"))
    )
    (net (code "109") (name "unconnected-(TP105-PP-PadTP)") (class "Default")
      (node (ref "TP105") (pin "TP") (pinfunction "PP_TP") (pintype "input"))
    )
    (net (code "110") (name "unconnected-(TP106-PP-PadTP)") (class "Default")
      (node (ref "TP106") (pin "TP") (pinfunction "PP_TP") (pintype "input"))
    )
    (net (code "111") (name "unconnected-(TP107-PP-PadTP)") (class "Default")
      (node (ref "TP107") (pin "TP") (pinfunction "PP_TP") (pintype "input"))
    )
    (net (code "112") (name "unconnected-(TP108-PP-PadTP)") (class "Default")
      (node (ref "TP108") (pin "TP") (pinfunction "PP_TP") (pintype "input"))
    )
    (net (code "113") (name "unconnected-(TP109-PP-PadTP)") (class "Default")
      (node (ref "TP109") (pin "TP") (pinfunction "PP_TP") (pintype "input"))
    )
    (net (code "114") (name "unconnected-(TP110-PP-PadTP)") (class "Default")
      (node (ref "TP110") (pin "TP") (pinfunction "PP_TP") (pintype "input"))
    )
    (net (code "115") (name "unconnected-(TP111-PP-PadTP)") (class "Default")
      (node (ref "TP111") (pin "TP") (pinfunction "PP_TP") (pintype "input"))
    )
    (net (code "116") (name "unconnected-(TP112-PP-PadTP)") (class "Default")
      (node (ref "TP112") (pin "TP") (pinfunction "PP_TP") (pintype "input"))
    )
    (net (code "117") (name "unconnected-(TP113-PP-PadTP)") (class "Default")
      (node (ref "TP113") (pin "TP") (pinfunction "PP_TP") (pintype "input"))
    )
    (net (code "118") (name "unconnected-(TP114-PP-PadTP)") (class "Default")
      (node (ref "TP114") (pin "TP") (pinfunction "PP_TP") (pintype "input"))
    )
    (net (code "119") (name "unconnected-(TP115-PP-PadTP)") (class "Default")
      (node (ref "TP115") (pin "TP") (pinfunction "PP_TP") (pintype "input"))
    )
    (net (code "120") (name "unconnected-(TP116-PP-PadTP)") (class "Default")
      (node (ref "TP116") (pin "TP") (pinfunction "PP_TP") (pintype "input"))
    )
    (net (code "121") (name "unconnected-(TP117-PP-PadTP)") (class "Default")
      (node (ref "TP117") (pin "TP") (pinfunction "PP_TP") (pintype "input"))
    )
    (net (code "122") (name "unconnected-(TP118-PP-PadTP)") (class "Default")
      (node (ref "TP118") (pin "TP") (pinfunction "PP_TP") (pintype "input"))
    )
    (net (code "123") (name "unconnected-(TP119-PP-PadTP)") (class "Default")
      (node (ref "TP119") (pin "TP") (pinfunction "PP_TP") (pintype "input"))
    )
    (net (code "124") (name "unconnected-(TP120-PP-PadTP)") (class "Default")
      (node (ref "TP120") (pin "TP") (pinfunction "PP_TP") (pintype "input"))
    )
    (net (code "125") (name "unconnected-(TP121-PP-PadTP)") (class "Default")
      (node (ref "TP121") (pin "TP") (pinfunction "PP_TP") (pintype "input"))
    )
    (net (code "126") (name "unconnected-(TP122-PP-PadTP)") (class "Default")
      (node (ref "TP122") (pin "TP") (pinfunction "PP_TP") (pintype "input"))
    )
    (net (code "127") (name "unconnected-(TP123-PP-PadTP)") (class "Default")
      (node (ref "TP123") (pin "TP") (pinfunction "PP_TP") (pintype "input"))
    )
    (net (code "128") (name "unconnected-(TP124-PP-PadTP)") (class "Default")
      (node (ref "TP124") (pin "TP") (pinfunction "PP_TP") (pintype "input"))
    )
    (net (code "129") (name "unconnected-(TP125-PP-PadTP)") (class "Default")
      (node (ref "TP125") (pin "TP") (pinfunction "PP_TP") (pintype "input"))
    )
    (net (code "130") (name "unconnected-(TP126-PP-PadTP)") (class "Default")
      (node (ref "TP126") (pin "TP") (pinfunction "PP_TP") (pintype "input"))
    )
    (net (code "131") (name "unconnected-(TP127-PP-PadTP)") (class "Default")
      (node (ref "TP127") (pin "TP") (pinfunction "PP_TP") (pintype "input"))
    )
    (net (code "132") (name "unconnected-(TP128-PP-PadTP)") (class "Default")
      (node (ref "TP128") (pin "TP") (pinfunction "PP_TP") (pintype "input"))
    )
    (net (code "133") (name "unconnected-(TP129-PP-PadTP)") (class "Default")
      (node (ref "TP129") (pin "TP") (pinfunction "PP_TP") (pintype "input"))
    )
    (net (code "134") (name "unconnected-(TP130-PP-PadTP)") (class "Default")
      (node (ref "TP130") (pin "TP") (pinfunction "PP_TP") (pintype "input"))
    )
    (net (code "135") (name "unconnected-(TP131-PP-PadTP)") (class "Default")
      (node (ref "TP131") (pin "TP") (pinfunction "PP_TP") (pintype "input"))
    )
    (net (code "136") (name "unconnected-(TP132-PP-PadTP)") (class "Default")
      (node (ref "TP132") (pin "TP") (pinfunction "PP_TP") (pintype "input"))
    )
    (net (code "137") (name "unconnected-(TP133-PP-PadTP)") (class "Default")
      (node (ref "TP133") (pin "TP") (pinfunction "PP_TP") (pintype "input"))
    )
    (net (code "138") (name "unconnected-(TP134-PP-PadTP)") (class "Default")
      (node (ref "TP134") (pin "TP") (pinfunction "PP_TP") (pintype "input"))
    )
    (net (code "139") (name "unconnected-(TP135-PP-PadTP)") (class "Default")
      (node (ref "TP135") (pin "TP") (pinfunction "PP_TP") (pintype "input"))
    )
    (net (code "140") (name "unconnected-(TP136-PP-PadTP)") (class "Default")
      (node (ref "TP136") (pin "TP") (pinfunction "PP_TP") (pintype "input"))
    )
    (net (code "141") (name "unconnected-(TP137-PP-PadTP)") (class "Default")
      (node (ref "TP137") (pin "TP") (pinfunction "PP_TP") (pintype "input"))
    )
    (net (code "142") (name "unconnected-(TP138-PP-PadTP)") (class "Default")
      (node (ref "TP138") (pin "TP") (pinfunction "PP_TP") (pintype "input"))
    )
    (net (code "143") (name "unconnected-(TP139-PP-PadTP)") (class "Default")
      (node (ref "TP139") (pin "TP") (pinfunction "PP_TP") (pintype "input"))
    )
    (net (code "144") (name "unconnected-(TP140-PP-PadTP)") (class "Default")
      (node (ref "TP140") (pin "TP") (pinfunction "PP_TP") (pintype "input"))
    )
    (net (code "145") (name "unconnected-(TP141-PP-PadTP)") (class "Default")
      (node (ref "TP141") (pin "TP") (pinfunction "PP_TP") (pintype "input"))
    )
    (net (code "146") (name "unconnected-(TP142-PP-PadTP)") (class "Default")
      (node (ref "TP142") (pin "TP") (pinfunction "PP_TP") (pintype "input"))
    )
    (net (code "147") (name "unconnected-(TP143-PP-PadTP)") (class "Default")
      (node (ref "TP143") (pin "TP") (pinfunction "PP_TP") (pintype "input"))
    )
    (net (code "148") (name "unconnected-(TP144-PP-PadTP)") (class "Default")
      (node (ref "TP144") (pin "TP") (pinfunction "PP_TP") (pintype "input"))
    )
    (net (code "149") (name "unconnected-(TP145-PP-PadTP)") (class "Default")
      (node (ref "TP145") (pin "TP") (pinfunction "PP_TP") (pintype "input"))
    )
    (net (code "150") (name "unconnected-(TP146-PP-PadTP)") (class "Default")
      (node (ref "TP146") (pin "TP") (pinfunction "PP_TP") (pintype "input"))
    )
    (net (code "151") (name "unconnected-(TP147-PP-PadTP)") (class "Default")
      (node (ref "TP147") (pin "TP") (pinfunction "PP_TP") (pintype "input"))
    )
    (net (code "152") (name "unconnected-(TP148-PP-PadTP)") (class "Default")
      (node (ref "TP148") (pin "TP") (pinfunction "PP_TP") (pintype "input"))
    )
    (net (code "153") (name "unconnected-(TP149-PP-PadTP)") (class "Default")
      (node (ref "TP149") (pin "TP") (pinfunction "PP_TP") (pintype "input"))
    )
    (net (code "154") (name "unconnected-(TP150-PP-PadTP)") (class "Default")
      (node (ref "TP150") (pin "TP") (pinfunction "PP_TP") (pintype "input"))
    )
    (net (code "155") (name "unconnected-(TP151-PP-PadTP)") (class "Default")
      (node (ref "TP151") (pin "TP") (pinfunction "PP_TP") (pintype "input"))
    )
    (net (code "156") (name "unconnected-(TP152-PP-PadTP)") (class "Default")
      (node (ref "TP152") (pin "TP") (pinfunction "PP_TP") (pintype "input"))
    )
    (net (code "157") (name "unconnected-(TP153-PP-PadTP)") (class "Default")
      (node (ref "TP153") (pin "TP") (pinfunction "PP_TP") (pintype "input"))
    )
    (net (code "158") (name "unconnected-(TP154-PP-PadTP)") (class "Default")
      (node (ref "TP154") (pin "TP") (pinfunction "PP_TP") (pintype "input"))
    )
    (net (code "159") (name "unconnected-(TP155-PP-PadTP)") (class "Default")
      (node (ref "TP155") (pin "TP") (pinfunction "PP_TP") (pintype "input"))
    )
    (net (code "160") (name "unconnected-(TP156-PP-PadTP)") (class "Default")
      (node (ref "TP156") (pin "TP") (pinfunction "PP_TP") (pintype "input"))
    )
    (net (code "161") (name "unconnected-(TP157-PP-PadTP)") (class "Default")
      (node (ref "TP157") (pin "TP") (pinfunction "PP_TP") (pintype "input"))
    )
    (net (code "162") (name "unconnected-(TP158-PP-PadTP)") (class "Default")
      (node (ref "TP158") (pin "TP") (pinfunction "PP_TP") (pintype "input"))
    )
    (net (code "163") (name "unconnected-(TP159-PP-PadTP)") (class "Default")
      (node (ref "TP159") (pin "TP") (pinfunction "PP_TP") (pintype "input"))
    )
    (net (code "164") (name "unconnected-(TP160-PP-PadTP)") (class "Default")
      (node (ref "TP160") (pin "TP") (pinfunction "PP_TP") (pintype "input"))
    )
    (net (code "165") (name "unconnected-(X1-Pad2)") (class "Default")
      (node (ref "X1") (pin "2") (pinfunction "2_2") (pintype "passive"))
    )
    (net (code "166") (name "unconnected-(X1-Pad3)") (class "Default")
      (node (ref "X1") (pin "3") (pinfunction "3_3") (pintype "passive"))
    )
    (net (code "167") (name "unconnected-(X1-Pad4)") (class "Default")
      (node (ref "X1") (pin "4") (pinfunction "4_4") (pintype "passive"))
    )
  )
)
